# RP_ComputeModule3_rev_3_0_Headers.net
KiCad netlist of a schematic drawn in Altium Designer
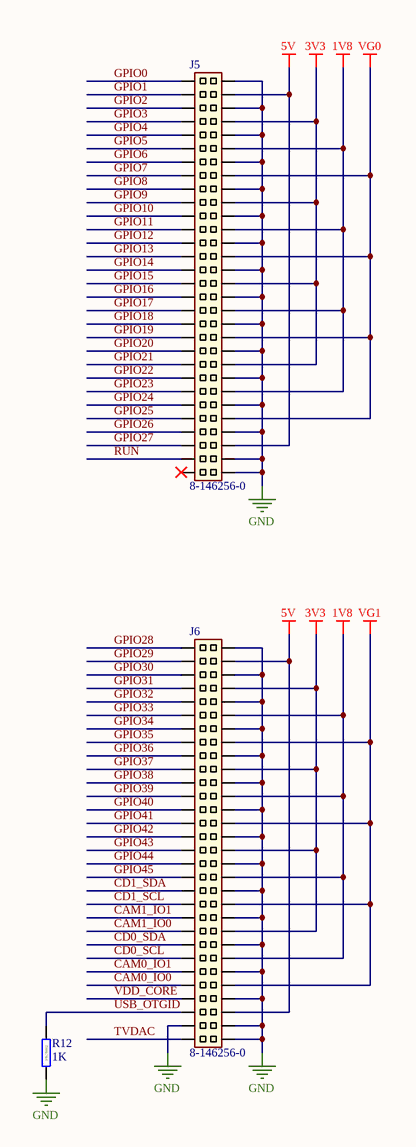
[diagram p0: RP_ComputeModule3_rev.3.0_Headers.SchDoc]

(export (version "E")
  (design (tool "Eeschema 10.0.6"))
  (components
    (comp (ref "J5")
      (value "8-146256-0")
      (footprint "TE 2x30 PINS 8-146256-0")
      (description "Headers & Wire Housings 60 MODII HDR DRST B/A .100CL LF")
      (fields (field (name "MANUFACTURER") "TE Connectivity"))
      (libsource (lib "TEConnectivity_AMP") (part "8-146256-0"))
    )
    (comp (ref "J6")
      (value "8-146256-0")
      (footprint "TE 2x30 PINS 8-146256-0")
      (description "Headers & Wire Housings 60 MODII HDR DRST B/A .100CL LF")
      (fields (field (name "MANUFACTURER") "TE Connectivity"))
      (libsource (lib "TEConnectivity_AMP") (part "8-146256-0"))
    )
    (comp (ref "R12")
      (value "1K")
      (footprint "RES0402")
      (description "Thick Film Resistors - SMD 1/3W 1K OHM 1%")
      (fields
        (field (name "MANUFACTURER") "KOA Speer")
        (field (name "MANUFACTURER PART NUMBER") "RK73H1FTTBL1001F")
      )
      (libsource (lib "KOA_Resistors") (part "RK73H1FTTBL1001F"))
    )
  )
  (nets
    (net (code "1") (name "/CAM0_IO0") (class "Default")
      (node (ref "J6") (pin "51") (pinfunction "51_51") (pintype "passive"))
    )
    (net (code "2") (name "/CAM0_IO1") (class "Default")
      (node (ref "J6") (pin "49") (pinfunction "49_49") (pintype "passive"))
    )
    (net (code "3") (name "/CAM1_IO0") (class "Default")
      (node (ref "J6") (pin "43") (pinfunction "43_43") (pintype "passive"))
    )
    (net (code "4") (name "/CAM1_IO1") (class "Default")
      (node (ref "J6") (pin "41") (pinfunction "41_41") (pintype "passive"))
    )
    (net (code "5") (name "/CD0_SCL") (class "Default")
      (node (ref "J6") (pin "47") (pinfunction "47_47") (pintype "passive"))
    )
    (net (code "6") (name "/CD0_SDA") (class "Default")
      (node (ref "J6") (pin "45") (pinfunction "45_45") (pintype "passive"))
    )
    (net (code "7") (name "/CD1_SCL") (class "Default")
      (node (ref "J6") (pin "39") (pinfunction "39_39") (pintype "passive"))
    )
    (net (code "8") (name "/CD1_SDA") (class "Default")
      (node (ref "J6") (pin "37") (pinfunction "37_37") (pintype "passive"))
    )
    (net (code "9") (name "/GPIO0") (class "Default")
      (node (ref "J5") (pin "1") (pinfunction "1_1") (pintype "passive"))
    )
    (net (code "10") (name "/GPIO1") (class "Default")
      (node (ref "J5") (pin "3") (pinfunction "3_3") (pintype "passive"))
    )
    (net (code "11") (name "/GPIO2") (class "Default")
      (node (ref "J5") (pin "5") (pinfunction "5_5") (pintype "passive"))
    )
    (net (code "12") (name "/GPIO3") (class "Default")
      (node (ref "J5") (pin "7") (pinfunction "7_7") (pintype "passive"))
    )
    (net (code "13") (name "/GPIO4") (class "Default")
      (node (ref "J5") (pin "9") (pinfunction "9_9") (pintype "passive"))
    )
    (net (code "14") (name "/GPIO5") (class "Default")
      (node (ref "J5") (pin "11") (pinfunction "11_11") (pintype "passive"))
    )
    (net (code "15") (name "/GPIO6") (class "Default")
      (node (ref "J5") (pin "13") (pinfunction "13_13") (pintype "passive"))
    )
    (net (code "16") (name "/GPIO7") (class "Default")
      (node (ref "J5") (pin "15") (pinfunction "15_15") (pintype "passive"))
    )
    (net (code "17") (name "/GPIO8") (class "Default")
      (node (ref "J5") (pin "17") (pinfunction "17_17") (pintype "passive"))
    )
    (net (code "18") (name "/GPIO9") (class "Default")
      (node (ref "J5") (pin "19") (pinfunction "19_19") (pintype "passive"))
    )
    (net (code "19") (name "/GPIO10") (class "Default")
      (node (ref "J5") (pin "21") (pinfunction "21_21") (pintype "passive"))
    )
    (net (code "20") (name "/GPIO11") (class "Default")
      (node (ref "J5") (pin "23") (pinfunction "23_23") (pintype "passive"))
    )
    (net (code "21") (name "/GPIO12") (class "Default")
      (node (ref "J5") (pin "25") (pinfunction "25_25") (pintype "passive"))
    )
    (net (code "22") (name "/GPIO13") (class "Default")
      (node (ref "J5") (pin "27") (pinfunction "27_27") (pintype "passive"))
    )
    (net (code "23") (name "/GPIO14") (class "Default")
      (node (ref "J5") (pin "29") (pinfunction "29_29") (pintype "passive"))
    )
    (net (code "24") (name "/GPIO15") (class "Default")
      (node (ref "J5") (pin "31") (pinfunction "31_31") (pintype "passive"))
    )
    (net (code "25") (name "/GPIO16") (class "Default")
      (node (ref "J5") (pin "33") (pinfunction "33_33") (pintype "passive"))
    )
    (net (code "26") (name "/GPIO17") (class "Default")
      (node (ref "J5") (pin "35") (pinfunction "35_35") (pintype "passive"))
    )
    (net (code "27") (name "/GPIO18") (class "Default")
      (node (ref "J5") (pin "37") (pinfunction "37_37") (pintype "passive"))
    )
    (net (code "28") (name "/GPIO19") (class "Default")
      (node (ref "J5") (pin "39") (pinfunction "39_39") (pintype "passive"))
    )
    (net (code "29") (name "/GPIO20") (class "Default")
      (node (ref "J5") (pin "41") (pinfunction "41_41") (pintype "passive"))
    )
    (net (code "30") (name "/GPIO21") (class "Default")
      (node (ref "J5") (pin "43") (pinfunction "43_43") (pintype "passive"))
    )
    (net (code "31") (name "/GPIO22") (class "Default")
      (node (ref "J5") (pin "45") (pinfunction "45_45") (pintype "passive"))
    )
    (net (code "32") (name "/GPIO23") (class "Default")
      (node (ref "J5") (pin "47") (pinfunction "47_47") (pintype "passive"))
    )
    (net (code "33") (name "/GPIO24") (class "Default")
      (node (ref "J5") (pin "49") (pinfunction "49_49") (pintype "passive"))
    )
    (net (code "34") (name "/GPIO25") (class "Default")
      (node (ref "J5") (pin "51") (pinfunction "51_51") (pintype "passive"))
    )
    (net (code "35") (name "/GPIO26") (class "Default")
      (node (ref "J5") (pin "53") (pinfunction "53_53") (pintype "passive"))
    )
    (net (code "36") (name "/GPIO27") (class "Default")
      (node (ref "J5") (pin "55") (pinfunction "55_55") (pintype "passive"))
    )
    (net (code "37") (name "/GPIO28") (class "Default")
      (node (ref "J6") (pin "1") (pinfunction "1_1") (pintype "passive"))
    )
    (net (code "38") (name "/GPIO29") (class "Default")
      (node (ref "J6") (pin "3") (pinfunction "3_3") (pintype "passive"))
    )
    (net (code "39") (name "/GPIO30") (class "Default")
      (node (ref "J6") (pin "5") (pinfunction "5_5") (pintype "passive"))
    )
    (net (code "40") (name "/GPIO31") (class "Default")
      (node (ref "J6") (pin "7") (pinfunction "7_7") (pintype "passive"))
    )
    (net (code "41") (name "/GPIO32") (class "Default")
      (node (ref "J6") (pin "9") (pinfunction "9_9") (pintype "passive"))
    )
    (net (code "42") (name "/GPIO33") (class "Default")
      (node (ref "J6") (pin "11") (pinfunction "11_11") (pintype "passive"))
    )
    (net (code "43") (name "/GPIO34") (class "Default")
      (node (ref "J6") (pin "13") (pinfunction "13_13") (pintype "passive"))
    )
    (net (code "44") (name "/GPIO35") (class "Default")
      (node (ref "J6") (pin "15") (pinfunction "15_15") (pintype "passive"))
    )
    (net (code "45") (name "/GPIO36") (class "Default")
      (node (ref "J6") (pin "17") (pinfunction "17_17") (pintype "passive"))
    )
    (net (code "46") (name "/GPIO37") (class "Default")
      (node (ref "J6") (pin "19") (pinfunction "19_19") (pintype "passive"))
    )
    (net (code "47") (name "/GPIO38") (class "Default")
      (node (ref "J6") (pin "21") (pinfunction "21_21") (pintype "passive"))
    )
    (net (code "48") (name "/GPIO39") (class "Default")
      (node (ref "J6") (pin "23") (pinfunction "23_23") (pintype "passive"))
    )
    (net (code "49") (name "/GPIO40") (class "Default")
      (node (ref "J6") (pin "25") (pinfunction "25_25") (pintype "passive"))
    )
    (net (code "50") (name "/GPIO41") (class "Default")
      (node (ref "J6") (pin "27") (pinfunction "27_27") (pintype "passive"))
    )
    (net (code "51") (name "/GPIO42") (class "Default")
      (node (ref "J6") (pin "29") (pinfunction "29_29") (pintype "passive"))
    )
    (net (code "52") (name "/GPIO43") (class "Default")
      (node (ref "J6") (pin "31") (pinfunction "31_31") (pintype "passive"))
    )
    (net (code "53") (name "/GPIO44") (class "Default")
      (node (ref "J6") (pin "33") (pinfunction "33_33") (pintype "passive"))
    )
    (net (code "54") (name "/GPIO45") (class "Default")
      (node (ref "J6") (pin "35") (pinfunction "35_35") (pintype "passive"))
    )
    (net (code "55") (name "/RUN") (class "Default")
      (node (ref "J5") (pin "57") (pinfunction "57_57") (pintype "passive"))
    )
    (net (code "56") (name "/TVDAC") (class "Default")
      (node (ref "J6") (pin "59") (pinfunction "59_59") (pintype "passive"))
    )
    (net (code "57") (name "/USB_OTGID") (class "Default")
      (node (ref "J6") (pin "55") (pinfunction "55_55") (pintype "passive"))
      (node (ref "R12") (pin "1") (pinfunction "1_1") (pintype "passive"))
    )
    (net (code "58") (name "/VDD_CORE") (class "Default")
      (node (ref "J6") (pin "53") (pinfunction "53_53") (pintype "passive"))
    )
    (net (code "59") (name "1V8") (class "Default")
      (node (ref "J5") (pin "12") (pinfunction "12_12") (pintype "passive"))
      (node (ref "J5") (pin "24") (pinfunction "24_24") (pintype "passive"))
      (node (ref "J5") (pin "36") (pinfunction "36_36") (pintype "passive"))
      (node (ref "J5") (pin "48") (pinfunction "48_48") (pintype "passive"))
      (node (ref "J6") (pin "12") (pinfunction "12_12") (pintype "passive"))
      (node (ref "J6") (pin "24") (pinfunction "24_24") (pintype "passive"))
      (node (ref "J6") (pin "36") (pinfunction "36_36") (pintype "passive"))
      (node (ref "J6") (pin "48") (pinfunction "48_48") (pintype "passive"))
    )
    (net (code "60") (name "3V3") (class "Default")
      (node (ref "J5") (pin "20") (pinfunction "20_20") (pintype "passive"))
      (node (ref "J5") (pin "32") (pinfunction "32_32") (pintype "passive"))
      (node (ref "J5") (pin "44") (pinfunction "44_44") (pintype "passive"))
      (node (ref "J5") (pin "8") (pinfunction "8_8") (pintype "passive"))
      (node (ref "J6") (pin "20") (pinfunction "20_20") (pintype "passive"))
      (node (ref "J6") (pin "32") (pinfunction "32_32") (pintype "passive"))
      (node (ref "J6") (pin "44") (pinfunction "44_44") (pintype "passive"))
      (node (ref "J6") (pin "8") (pinfunction "8_8") (pintype "passive"))
    )
    (net (code "61") (name "5V") (class "Default")
      (node (ref "J5") (pin "4") (pinfunction "4_4") (pintype "passive"))
      (node (ref "J5") (pin "56") (pinfunction "56_56") (pintype "passive"))
      (node (ref "J6") (pin "4") (pinfunction "4_4") (pintype "passive"))
      (node (ref "J6") (pin "56") (pinfunction "56_56") (pintype "passive"))
    )
    (net (code "62") (name "GND") (class "Default")
      (node (ref "J5") (pin "10") (pinfunction "10_10") (pintype "passive"))
      (node (ref "J5") (pin "14") (pinfunction "14_14") (pintype "passive"))
      (node (ref "J5") (pin "18") (pinfunction "18_18") (pintype "passive"))
      (node (ref "J5") (pin "2") (pinfunction "2_2") (pintype "passive"))
      (node (ref "J5") (pin "22") (pinfunction "22_22") (pintype "passive"))
      (node (ref "J5") (pin "26") (pinfunction "26_26") (pintype "passive"))
      (node (ref "J5") (pin "30") (pinfunction "30_30") (pintype "passive"))
      (node (ref "J5") (pin "34") (pinfunction "34_34") (pintype "passive"))
      (node (ref "J5") (pin "38") (pinfunction "38_38") (pintype "passive"))
      (node (ref "J5") (pin "42") (pinfunction "42_42") (pintype "passive"))
      (node (ref "J5") (pin "46") (pinfunction "46_46") (pintype "passive"))
      (node (ref "J5") (pin "50") (pinfunction "50_50") (pintype "passive"))
      (node (ref "J5") (pin "54") (pinfunction "54_54") (pintype "passive"))
      (node (ref "J5") (pin "58") (pinfunction "58_58") (pintype "passive"))
      (node (ref "J5") (pin "6") (pinfunction "6_6") (pintype "passive"))
      (node (ref "J5") (pin "60") (pinfunction "60_60") (pintype "passive"))
      (node (ref "J6") (pin "10") (pinfunction "10_10") (pintype "passive"))
      (node (ref "J6") (pin "14") (pinfunction "14_14") (pintype "passive"))
      (node (ref "J6") (pin "18") (pinfunction "18_18") (pintype "passive"))
      (node (ref "J6") (pin "2") (pinfunction "2_2") (pintype "passive"))
      (node (ref "J6") (pin "22") (pinfunction "22_22") (pintype "passive"))
      (node (ref "J6") (pin "26") (pinfunction "26_26") (pintype "passive"))
      (node (ref "J6") (pin "30") (pinfunction "30_30") (pintype "passive"))
      (node (ref "J6") (pin "34") (pinfunction "34_34") (pintype "passive"))
      (node (ref "J6") (pin "38") (pinfunction "38_38") (pintype "passive"))
      (node (ref "J6") (pin "42") (pinfunction "42_42") (pintype "passive"))
      (node (ref "J6") (pin "46") (pinfunction "46_46") (pintype "passive"))
      (node (ref "J6") (pin "50") (pinfunction "50_50") (pintype "passive"))
      (node (ref "J6") (pin "54") (pinfunction "54_54") (pintype "passive"))
      (node (ref "J6") (pin "57") (pinfunction "57_57") (pintype "passive"))
      (node (ref "J6") (pin "58") (pinfunction "58_58") (pintype "passive"))
      (node (ref "J6") (pin "6") (pinfunction "6_6") (pintype "passive"))
      (node (ref "J6") (pin "60") (pinfunction "60_60") (pintype "passive"))
      (node (ref "R12") (pin "2") (pinfunction "2_2") (pintype "passive"))
    )
    (net (code "63") (name "VG0") (class "Default")
      (node (ref "J5") (pin "16") (pinfunction "16_16") (pintype "passive"))
      (node (ref "J5") (pin "28") (pinfunction "28_28") (pintype "passive"))
      (node (ref "J5") (pin "40") (pinfunction "40_40") (pintype "passive"))
      (node (ref "J5") (pin "52") (pinfunction "52_52") (pintype "passive"))
    )
    (net (code "64") (name "VG1") (class "Default")
      (node (ref "J6") (pin "16") (pinfunction "16_16") (pintype "passive"))
      (node (ref "J6") (pin "28") (pinfunction "28_28") (pintype "passive"))
      (node (ref "J6") (pin "40") (pinfunction "40_40") (pintype "passive"))
      (node (ref "J6") (pin "52") (pinfunction "52_52") (pintype "passive"))
    )
    (net (code "65") (name "unconnected-(J5-Pad59)") (class "Default")
      (node (ref "J5") (pin "59") (pinfunction "59_59") (pintype "passive+no_connect"))
    )
  )
)
